# 15_HD_PUMP.net
KiCad netlist of a schematic drawn in Altium Designer
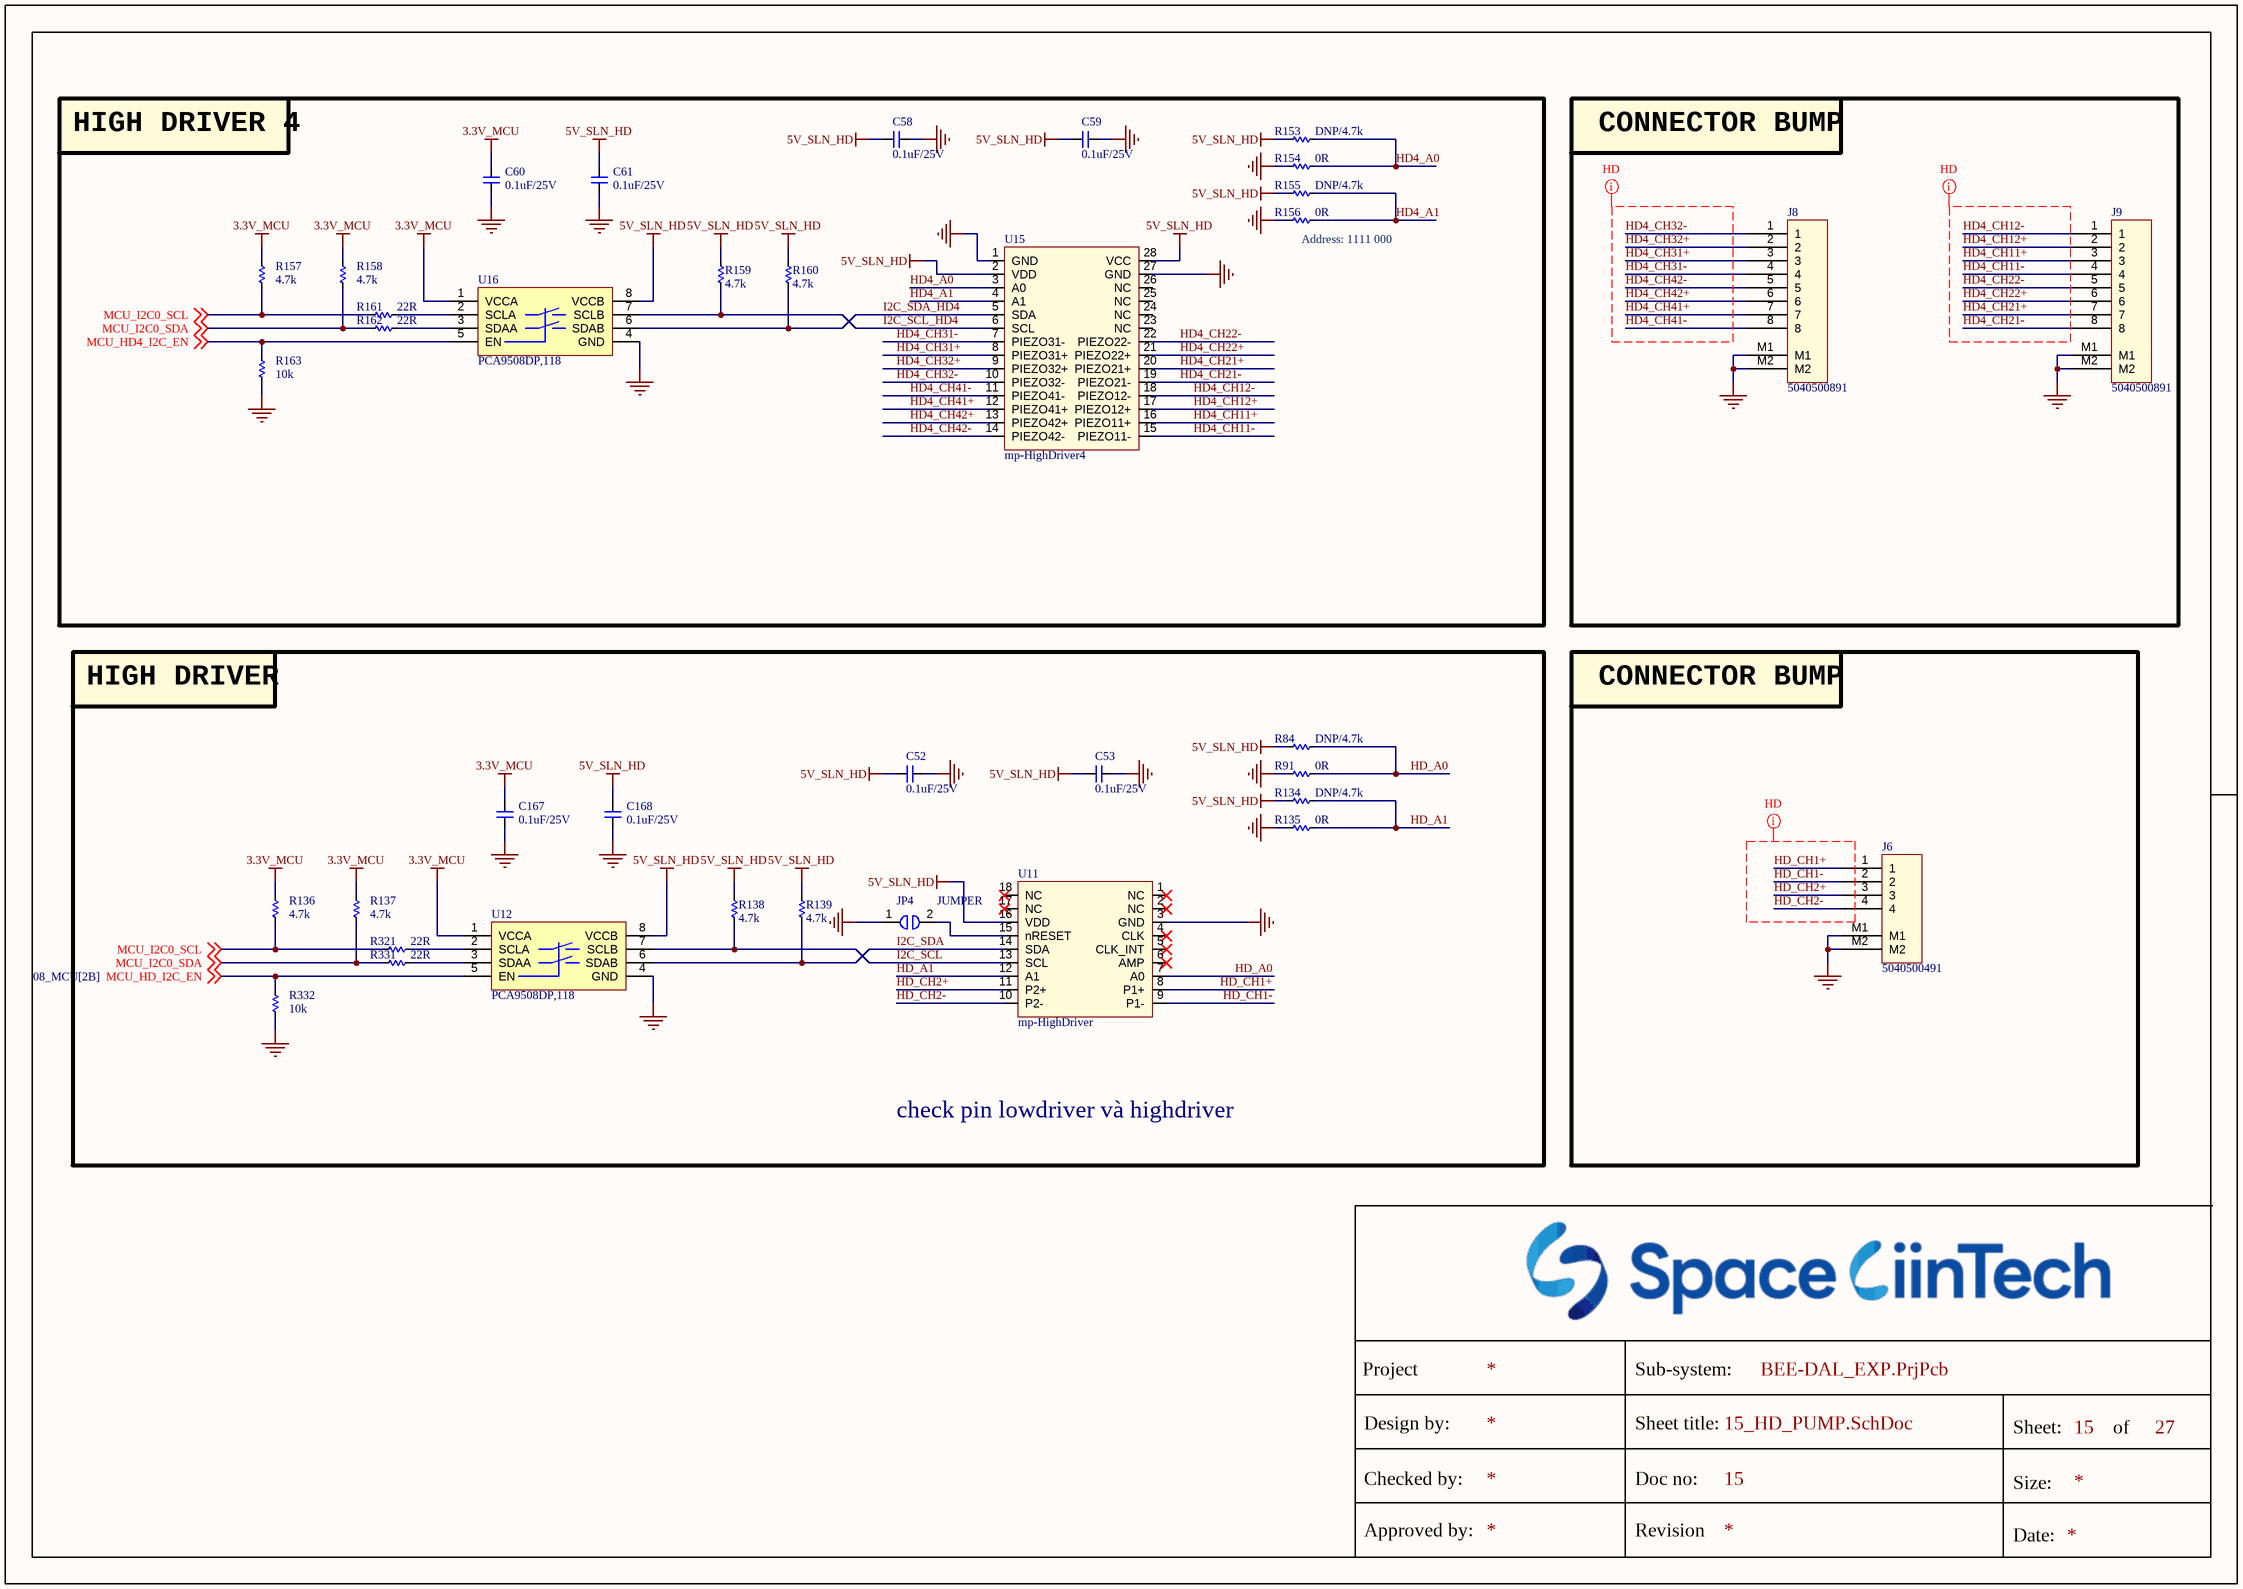
[diagram p0: 15_HD_PUMP.SchDoc]

(export (version "E")
  (design (tool "Eeschema 10.0.6"))
  (components
    (comp (ref "C52")
      (value "0.1uF/25V")
      (footprint "CAP_C_1005X60")
      (description "CAP")
      (libsource (lib "LABLIB") (part "_CAP_C_2"))
    )
    (comp (ref "C53")
      (value "0.1uF/25V")
      (footprint "CAP_C_1005X60")
      (description "CAP")
      (libsource (lib "LABLIB") (part "_CAP_C_2"))
    )
    (comp (ref "C58")
      (value "0.1uF/25V")
      (footprint "CAP_C_1005X60")
      (description "CAP")
      (libsource (lib "LABLIB") (part "_CAP_C_2"))
    )
    (comp (ref "C59")
      (value "0.1uF/25V")
      (footprint "CAP_C_1005X60")
      (description "CAP")
      (libsource (lib "LABLIB") (part "_CAP_C_2"))
    )
    (comp (ref "C60")
      (value "0.1uF/25V")
      (footprint "CAP_C_1005X60")
      (description "CAP")
      (libsource (lib "LABLIB") (part "_CAP_C_2"))
    )
    (comp (ref "C61")
      (value "0.1uF/25V")
      (footprint "CAP_C_1005X60")
      (description "CAP")
      (libsource (lib "LABLIB") (part "_CAP_C_2"))
    )
    (comp (ref "C167")
      (value "0.1uF/25V")
      (footprint "CAP_C_1005X60")
      (description "CAP")
      (libsource (lib "LABLIB") (part "_CAP_C_2"))
    )
    (comp (ref "C168")
      (value "0.1uF/25V")
      (footprint "CAP_C_1005X60")
      (description "CAP")
      (libsource (lib "LABLIB") (part "_CAP_C_2"))
    )
    (comp (ref "J6")
      (value "5040500491")
      (footprint "MOLEX_5040500491")
      (libsource (lib "LABLIB") (part "Header 4x1_2M"))
    )
    (comp (ref "J8")
      (value "5040500891")
      (footprint "MOLEX_5040500891")
      (libsource (lib "LABLIB") (part "Header 8x1_2M"))
    )
    (comp (ref "J9")
      (value "5040500891")
      (footprint "MOLEX_5040500891")
      (libsource (lib "LABLIB") (part "Header 8x1_2M"))
    )
    (comp (ref "JP4")
      (value "JUMPER")
      (footprint "JUMPER_1608")
      (libsource (lib "BEE-DAL_EXP_sche") (part "JUMPER_1_1"))
    )
    (comp (ref "R84")
      (value "DNP/4.7k")
      (footprint "RES_C_1005X40")
      (description "RES")
      (libsource (lib "LABLIB") (part "_RES_B_2"))
    )
    (comp (ref "R91")
      (value "0R")
      (footprint "RES_C_1005X40")
      (description "RES")
      (libsource (lib "LABLIB") (part "_RES_B_2"))
    )
    (comp (ref "R134")
      (value "DNP/4.7k")
      (footprint "RES_C_1005X40")
      (description "RES")
      (libsource (lib "LABLIB") (part "_RES_B_2"))
    )
    (comp (ref "R135")
      (value "0R")
      (footprint "RES_C_1005X40")
      (description "RES")
      (libsource (lib "LABLIB") (part "_RES_B_2"))
    )
    (comp (ref "R136")
      (value "4.7k")
      (footprint "RES_C_1005X40")
      (description "RES")
      (libsource (lib "LABLIB") (part "_RES_B_2"))
    )
    (comp (ref "R137")
      (value "4.7k")
      (footprint "RES_C_1005X40")
      (description "RES")
      (libsource (lib "LABLIB") (part "_RES_B_2"))
    )
    (comp (ref "R138")
      (value "4.7k")
      (footprint "RES_C_1005X40")
      (description "RES")
      (libsource (lib "LABLIB") (part "_RES_B_2"))
    )
    (comp (ref "R139")
      (value "4.7k")
      (footprint "RES_C_1005X40")
      (description "RES")
      (libsource (lib "LABLIB") (part "_RES_B_2"))
    )
    (comp (ref "R153")
      (value "DNP/4.7k")
      (footprint "RES_C_1005X40")
      (description "RES")
      (libsource (lib "LABLIB") (part "_RES_B_2"))
    )
    (comp (ref "R154")
      (value "0R")
      (footprint "RES_C_1005X40")
      (description "RES")
      (libsource (lib "LABLIB") (part "_RES_B_2"))
    )
    (comp (ref "R155")
      (value "DNP/4.7k")
      (footprint "RES_C_1005X40")
      (description "RES")
      (libsource (lib "LABLIB") (part "_RES_B_2"))
    )
    (comp (ref "R156")
      (value "0R")
      (footprint "RES_C_1005X40")
      (description "RES")
      (libsource (lib "LABLIB") (part "_RES_B_2"))
    )
    (comp (ref "R157")
      (value "4.7k")
      (footprint "RES_C_1005X40")
      (description "RES")
      (libsource (lib "LABLIB") (part "_RES_B_2"))
    )
    (comp (ref "R158")
      (value "4.7k")
      (footprint "RES_C_1005X40")
      (description "RES")
      (libsource (lib "LABLIB") (part "_RES_B_2"))
    )
    (comp (ref "R159")
      (value "4.7k")
      (footprint "RES_C_1005X40")
      (description "RES")
      (libsource (lib "LABLIB") (part "_RES_B_2"))
    )
    (comp (ref "R160")
      (value "4.7k")
      (footprint "RES_C_1005X40")
      (description "RES")
      (libsource (lib "LABLIB") (part "_RES_B_2"))
    )
    (comp (ref "R161")
      (value "22R")
      (footprint "RES_C_1005X40")
      (description "RES")
      (libsource (lib "LABLIB") (part "_RES_B_2"))
    )
    (comp (ref "R162")
      (value "22R")
      (footprint "RES_C_1005X40")
      (description "RES")
      (libsource (lib "LABLIB") (part "_RES_B_2"))
    )
    (comp (ref "R163")
      (value "10k")
      (footprint "RES_C_1005X40")
      (description "RES")
      (libsource (lib "LABLIB") (part "_RES_B_2"))
    )
    (comp (ref "R321")
      (value "22R")
      (footprint "RES_C_1005X40")
      (description "RES")
      (libsource (lib "LABLIB") (part "_RES_B_2"))
    )
    (comp (ref "R331")
      (value "22R")
      (footprint "RES_C_1005X40")
      (description "RES")
      (libsource (lib "LABLIB") (part "_RES_B_2"))
    )
    (comp (ref "R332")
      (value "10k")
      (footprint "RES_C_1005X40")
      (description "RES")
      (libsource (lib "LABLIB") (part "_RES_B_2"))
    )
    (comp (ref "U11")
      (value "mp-HighDriver")
      (footprint "MP_HIGHDRIVER")
      (libsource (lib "LABLIB") (part "mp-HighDriver"))
    )
    (comp (ref "U12")
      (value "PCA9508DP,118")
      (footprint "TSOP8")
      (libsource (lib "BEE-DAL_EXP_sche") (part "PCA9508DP,118"))
    )
    (comp (ref "U15")
      (value "mp-HighDriver4")
      (footprint "MP_HIGHDRIVER4")
      (libsource (lib "BEE-DAL_EXP_sche") (part "mp_HighDriver4"))
    )
    (comp (ref "U16")
      (value "PCA9508DP,118")
      (footprint "TSOP8")
      (libsource (lib "BEE-DAL_EXP_sche") (part "PCA9508DP,118"))
    )
  )
  (nets
    (net (code "1") (name "/HD4_A0") (class "Default")
      (node (ref "R153") (pin "2") (pinfunction "2_2") (pintype "passive"))
      (node (ref "R154") (pin "2") (pinfunction "2_2") (pintype "passive"))
      (node (ref "U15") (pin "3") (pinfunction "A0_3") (pintype "passive"))
    )
    (net (code "2") (name "/HD4_A1") (class "Default")
      (node (ref "R155") (pin "2") (pinfunction "2_2") (pintype "passive"))
      (node (ref "R156") (pin "2") (pinfunction "2_2") (pintype "passive"))
      (node (ref "U15") (pin "4") (pinfunction "A1_4") (pintype "passive"))
    )
    (net (code "3") (name "/HD4_CH11+") (class "Default")
      (node (ref "J9") (pin "3") (pinfunction "3_3") (pintype "passive"))
      (node (ref "U15") (pin "16") (pinfunction "PIEZO11+_16") (pintype "passive"))
    )
    (net (code "4") (name "/HD4_CH11-") (class "Default")
      (node (ref "J9") (pin "4") (pinfunction "4_4") (pintype "passive"))
      (node (ref "U15") (pin "15") (pinfunction "PIEZO11-_15") (pintype "passive"))
    )
    (net (code "5") (name "/HD4_CH12+") (class "Default")
      (node (ref "J9") (pin "2") (pinfunction "2_2") (pintype "passive"))
      (node (ref "U15") (pin "17") (pinfunction "PIEZO12+_17") (pintype "passive"))
    )
    (net (code "6") (name "/HD4_CH12-") (class "Default")
      (node (ref "J9") (pin "1") (pinfunction "1_1") (pintype "passive"))
      (node (ref "U15") (pin "18") (pinfunction "PIEZO12-_18") (pintype "passive"))
    )
    (net (code "7") (name "/HD4_CH21+") (class "Default")
      (node (ref "J9") (pin "7") (pinfunction "7_7") (pintype "passive"))
      (node (ref "U15") (pin "20") (pinfunction "PIEZO21+_20") (pintype "passive"))
    )
    (net (code "8") (name "/HD4_CH21-") (class "Default")
      (node (ref "J9") (pin "8") (pinfunction "8_8") (pintype "passive"))
      (node (ref "U15") (pin "19") (pinfunction "PIEZO21-_19") (pintype "passive"))
    )
    (net (code "9") (name "/HD4_CH22+") (class "Default")
      (node (ref "J9") (pin "6") (pinfunction "6_6") (pintype "passive"))
      (node (ref "U15") (pin "21") (pinfunction "PIEZO22+_21") (pintype "passive"))
    )
    (net (code "10") (name "/HD4_CH22-") (class "Default")
      (node (ref "J9") (pin "5") (pinfunction "5_5") (pintype "passive"))
      (node (ref "U15") (pin "22") (pinfunction "PIEZO22-_22") (pintype "passive"))
    )
    (net (code "11") (name "/HD4_CH31+") (class "Default")
      (node (ref "J8") (pin "3") (pinfunction "3_3") (pintype "passive"))
      (node (ref "U15") (pin "8") (pinfunction "PIEZO31+_8") (pintype "passive"))
    )
    (net (code "12") (name "/HD4_CH31-") (class "Default")
      (node (ref "J8") (pin "4") (pinfunction "4_4") (pintype "passive"))
      (node (ref "U15") (pin "7") (pinfunction "PIEZO31-_7") (pintype "passive"))
    )
    (net (code "13") (name "/HD4_CH32+") (class "Default")
      (node (ref "J8") (pin "2") (pinfunction "2_2") (pintype "passive"))
      (node (ref "U15") (pin "9") (pinfunction "PIEZO32+_9") (pintype "passive"))
    )
    (net (code "14") (name "/HD4_CH32-") (class "Default")
      (node (ref "J8") (pin "1") (pinfunction "1_1") (pintype "passive"))
      (node (ref "U15") (pin "10") (pinfunction "PIEZO32-_10") (pintype "passive"))
    )
    (net (code "15") (name "/HD4_CH41+") (class "Default")
      (node (ref "J8") (pin "7") (pinfunction "7_7") (pintype "passive"))
      (node (ref "U15") (pin "12") (pinfunction "PIEZO41+_12") (pintype "passive"))
    )
    (net (code "16") (name "/HD4_CH41-") (class "Default")
      (node (ref "J8") (pin "8") (pinfunction "8_8") (pintype "passive"))
      (node (ref "U15") (pin "11") (pinfunction "PIEZO41-_11") (pintype "passive"))
    )
    (net (code "17") (name "/HD4_CH42+") (class "Default")
      (node (ref "J8") (pin "6") (pinfunction "6_6") (pintype "passive"))
      (node (ref "U15") (pin "13") (pinfunction "PIEZO42+_13") (pintype "passive"))
    )
    (net (code "18") (name "/HD4_CH42-") (class "Default")
      (node (ref "J8") (pin "5") (pinfunction "5_5") (pintype "passive"))
      (node (ref "U15") (pin "14") (pinfunction "PIEZO42-_14") (pintype "passive"))
    )
    (net (code "19") (name "/HD_A0") (class "Default")
      (node (ref "R84") (pin "2") (pinfunction "2_2") (pintype "passive"))
      (node (ref "R91") (pin "2") (pinfunction "2_2") (pintype "passive"))
      (node (ref "U11") (pin "7") (pinfunction "A0_7") (pintype "passive"))
    )
    (net (code "20") (name "/HD_A1") (class "Default")
      (node (ref "R134") (pin "2") (pinfunction "2_2") (pintype "passive"))
      (node (ref "R135") (pin "2") (pinfunction "2_2") (pintype "passive"))
      (node (ref "U11") (pin "12") (pinfunction "A1_12") (pintype "passive"))
    )
    (net (code "21") (name "/HD_CH1+") (class "Default")
      (node (ref "J6") (pin "1") (pinfunction "1_1") (pintype "passive"))
      (node (ref "U11") (pin "8") (pinfunction "P1+_8") (pintype "passive"))
    )
    (net (code "22") (name "/HD_CH1-") (class "Default")
      (node (ref "J6") (pin "2") (pinfunction "2_2") (pintype "passive"))
      (node (ref "U11") (pin "9") (pinfunction "P1-_9") (pintype "passive"))
    )
    (net (code "23") (name "/HD_CH2+") (class "Default")
      (node (ref "J6") (pin "3") (pinfunction "3_3") (pintype "passive"))
      (node (ref "U11") (pin "11") (pinfunction "P2+_11") (pintype "passive"))
    )
    (net (code "24") (name "/HD_CH2-") (class "Default")
      (node (ref "J6") (pin "4") (pinfunction "4_4") (pintype "passive"))
      (node (ref "U11") (pin "10") (pinfunction "P2-_10") (pintype "passive"))
    )
    (net (code "25") (name "/I2C_SCL") (class "Default")
      (node (ref "R138") (pin "2") (pinfunction "2_2") (pintype "passive"))
      (node (ref "U11") (pin "13") (pinfunction "SCL_13") (pintype "passive"))
      (node (ref "U12") (pin "7") (pinfunction "SCLB_7") (pintype "passive"))
    )
    (net (code "26") (name "/I2C_SCL_HD4") (class "Default")
      (node (ref "R159") (pin "2") (pinfunction "2_2") (pintype "passive"))
      (node (ref "U15") (pin "6") (pinfunction "SCL_6") (pintype "passive"))
      (node (ref "U16") (pin "7") (pinfunction "SCLB_7") (pintype "passive"))
    )
    (net (code "27") (name "/I2C_SDA") (class "Default")
      (node (ref "R139") (pin "2") (pinfunction "2_2") (pintype "passive"))
      (node (ref "U11") (pin "14") (pinfunction "SDA_14") (pintype "passive"))
      (node (ref "U12") (pin "6") (pinfunction "SDAB_6") (pintype "passive"))
    )
    (net (code "28") (name "/I2C_SDA_HD4") (class "Default")
      (node (ref "R160") (pin "2") (pinfunction "2_2") (pintype "passive"))
      (node (ref "U15") (pin "5") (pinfunction "SDA_5") (pintype "passive"))
      (node (ref "U16") (pin "6") (pinfunction "SDAB_6") (pintype "passive"))
    )
    (net (code "29") (name "3.3V_MCU") (class "Default")
      (node (ref "C167") (pin "2") (pinfunction "2_2") (pintype "passive"))
      (node (ref "C60") (pin "2") (pinfunction "2_2") (pintype "passive"))
      (node (ref "R136") (pin "1") (pinfunction "1_1") (pintype "passive"))
      (node (ref "R137") (pin "1") (pinfunction "1_1") (pintype "passive"))
      (node (ref "R157") (pin "1") (pinfunction "1_1") (pintype "passive"))
      (node (ref "R158") (pin "1") (pinfunction "1_1") (pintype "passive"))
      (node (ref "U12") (pin "1") (pinfunction "VCCA_1") (pintype "passive"))
      (node (ref "U16") (pin "1") (pinfunction "VCCA_1") (pintype "passive"))
    )
    (net (code "30") (name "5V_SLN_HD") (class "Default")
      (node (ref "C168") (pin "2") (pinfunction "2_2") (pintype "passive"))
      (node (ref "C52") (pin "2") (pinfunction "2_2") (pintype "passive"))
      (node (ref "C53") (pin "2") (pinfunction "2_2") (pintype "passive"))
      (node (ref "C58") (pin "2") (pinfunction "2_2") (pintype "passive"))
      (node (ref "C59") (pin "2") (pinfunction "2_2") (pintype "passive"))
      (node (ref "C61") (pin "2") (pinfunction "2_2") (pintype "passive"))
      (node (ref "R134") (pin "1") (pinfunction "1_1") (pintype "passive"))
      (node (ref "R138") (pin "1") (pinfunction "1_1") (pintype "passive"))
      (node (ref "R139") (pin "1") (pinfunction "1_1") (pintype "passive"))
      (node (ref "R153") (pin "1") (pinfunction "1_1") (pintype "passive"))
      (node (ref "R155") (pin "1") (pinfunction "1_1") (pintype "passive"))
      (node (ref "R159") (pin "1") (pinfunction "1_1") (pintype "passive"))
      (node (ref "R160") (pin "1") (pinfunction "1_1") (pintype "passive"))
      (node (ref "R84") (pin "1") (pinfunction "1_1") (pintype "passive"))
      (node (ref "U11") (pin "16") (pinfunction "VDD_16") (pintype "power_in"))
      (node (ref "U12") (pin "8") (pinfunction "VCCB_8") (pintype "passive"))
      (node (ref "U15") (pin "2") (pinfunction "VDD_2") (pintype "power_in"))
      (node (ref "U15") (pin "28") (pinfunction "VCC_28") (pintype "power_in"))
      (node (ref "U16") (pin "8") (pinfunction "VCCB_8") (pintype "passive"))
    )
    (net (code "31") (name "GND") (class "Default")
      (node (ref "C167") (pin "1") (pinfunction "1_1") (pintype "passive"))
      (node (ref "C168") (pin "1") (pinfunction "1_1") (pintype "passive"))
      (node (ref "C52") (pin "1") (pinfunction "1_1") (pintype "passive"))
      (node (ref "C53") (pin "1") (pinfunction "1_1") (pintype "passive"))
      (node (ref "C58") (pin "1") (pinfunction "1_1") (pintype "passive"))
      (node (ref "C59") (pin "1") (pinfunction "1_1") (pintype "passive"))
      (node (ref "C60") (pin "1") (pinfunction "1_1") (pintype "passive"))
      (node (ref "C61") (pin "1") (pinfunction "1_1") (pintype "passive"))
      (node (ref "J6") (pin "M1") (pinfunction "M1_M1") (pintype "passive"))
      (node (ref "J6") (pin "M2") (pinfunction "M2_M2") (pintype "passive"))
      (node (ref "J8") (pin "M1") (pinfunction "M1_M1") (pintype "passive"))
      (node (ref "J8") (pin "M2") (pinfunction "M2_M2") (pintype "passive"))
      (node (ref "J9") (pin "M1") (pinfunction "M1_M1") (pintype "passive"))
      (node (ref "J9") (pin "M2") (pinfunction "M2_M2") (pintype "passive"))
      (node (ref "JP4") (pin "1") (pinfunction "1_1") (pintype "passive"))
      (node (ref "R135") (pin "1") (pinfunction "1_1") (pintype "passive"))
      (node (ref "R154") (pin "1") (pinfunction "1_1") (pintype "passive"))
      (node (ref "R156") (pin "1") (pinfunction "1_1") (pintype "passive"))
      (node (ref "R163") (pin "2") (pinfunction "2_2") (pintype "passive"))
      (node (ref "R332") (pin "2") (pinfunction "2_2") (pintype "passive"))
      (node (ref "R91") (pin "1") (pinfunction "1_1") (pintype "passive"))
      (node (ref "U11") (pin "3") (pinfunction "GND_3") (pintype "power_in"))
      (node (ref "U12") (pin "4") (pinfunction "GND_4") (pintype "passive"))
      (node (ref "U15") (pin "1") (pinfunction "GND_1") (pintype "power_in"))
      (node (ref "U15") (pin "27") (pinfunction "GND_27") (pintype "power_in"))
      (node (ref "U16") (pin "4") (pinfunction "GND_4") (pintype "passive"))
    )
    (net (code "32") (name "MCU_HD4_I2C_EN") (class "Default")
      (node (ref "R163") (pin "1") (pinfunction "1_1") (pintype "passive"))
      (node (ref "U16") (pin "5") (pinfunction "EN_5") (pintype "passive"))
    )
    (net (code "33") (name "MCU_HD_I2C_EN") (class "Default")
      (node (ref "R332") (pin "1") (pinfunction "1_1") (pintype "passive"))
      (node (ref "U12") (pin "5") (pinfunction "EN_5") (pintype "passive"))
    )
    (net (code "34") (name "MCU_I2C0_SCL") (class "Default")
      (node (ref "R136") (pin "2") (pinfunction "2_2") (pintype "passive"))
      (node (ref "R157") (pin "2") (pinfunction "2_2") (pintype "passive"))
      (node (ref "R161") (pin "1") (pinfunction "1_1") (pintype "passive"))
      (node (ref "R321") (pin "1") (pinfunction "1_1") (pintype "passive"))
    )
    (net (code "35") (name "MCU_I2C0_SDA") (class "Default")
      (node (ref "R137") (pin "2") (pinfunction "2_2") (pintype "passive"))
      (node (ref "R158") (pin "2") (pinfunction "2_2") (pintype "passive"))
      (node (ref "R162") (pin "1") (pinfunction "1_1") (pintype "passive"))
      (node (ref "R331") (pin "1") (pinfunction "1_1") (pintype "passive"))
    )
    (net (code "36") (name "Net-(U11-nRESET)") (class "Default")
      (node (ref "JP4") (pin "2") (pinfunction "2_2") (pintype "passive"))
      (node (ref "U11") (pin "15") (pinfunction "nRESET_15") (pintype "passive"))
    )
    (net (code "37") (name "Net-(U12-SCLA)") (class "Default")
      (node (ref "R321") (pin "2") (pinfunction "2_2") (pintype "passive"))
      (node (ref "U12") (pin "2") (pinfunction "SCLA_2") (pintype "passive"))
    )
    (net (code "38") (name "Net-(U12-SDAA)") (class "Default")
      (node (ref "R331") (pin "2") (pinfunction "2_2") (pintype "passive"))
      (node (ref "U12") (pin "3") (pinfunction "SDAA_3") (pintype "passive"))
    )
    (net (code "39") (name "Net-(U16-SCLA)") (class "Default")
      (node (ref "R161") (pin "2") (pinfunction "2_2") (pintype "passive"))
      (node (ref "U16") (pin "2") (pinfunction "SCLA_2") (pintype "passive"))
    )
    (net (code "40") (name "Net-(U16-SDAA)") (class "Default")
      (node (ref "R162") (pin "2") (pinfunction "2_2") (pintype "passive"))
      (node (ref "U16") (pin "3") (pinfunction "SDAA_3") (pintype "passive"))
    )
    (net (code "41") (name "unconnected-(U11-AMP-Pad6)") (class "Default")
      (node (ref "U11") (pin "6") (pinfunction "AMP_6") (pintype "passive+no_connect"))
    )
    (net (code "42") (name "unconnected-(U11-CLK-Pad4)") (class "Default")
      (node (ref "U11") (pin "4") (pinfunction "CLK_4") (pintype "passive+no_connect"))
    )
    (net (code "43") (name "unconnected-(U11-CLK_INT-Pad5)") (class "Default")
      (node (ref "U11") (pin "5") (pinfunction "CLK_INT_5") (pintype "passive+no_connect"))
    )
    (net (code "44") (name "unconnected-(U11-NC-Pad1)") (class "Default")
      (node (ref "U11") (pin "1") (pinfunction "NC_1") (pintype "passive+no_connect"))
    )
    (net (code "45") (name "unconnected-(U11-NC-Pad2)") (class "Default")
      (node (ref "U11") (pin "2") (pinfunction "NC_2") (pintype "passive+no_connect"))
    )
    (net (code "46") (name "unconnected-(U11-NC-Pad17)") (class "Default")
      (node (ref "U11") (pin "17") (pinfunction "NC_17") (pintype "passive+no_connect"))
    )
    (net (code "47") (name "unconnected-(U11-NC-Pad18)") (class "Default")
      (node (ref "U11") (pin "18") (pinfunction "NC_18") (pintype "passive+no_connect"))
    )
    (net (code "48") (name "unconnected-(U15-NC-Pad23)") (class "Default")
      (node (ref "U15") (pin "23") (pinfunction "NC_23") (pintype "passive"))
    )
    (net (code "49") (name "unconnected-(U15-NC-Pad24)") (class "Default")
      (node (ref "U15") (pin "24") (pinfunction "NC_24") (pintype "passive"))
    )
    (net (code "50") (name "unconnected-(U15-NC-Pad25)") (class "Default")
      (node (ref "U15") (pin "25") (pinfunction "NC_25") (pintype "passive"))
    )
    (net (code "51") (name "unconnected-(U15-NC-Pad26)") (class "Default")
      (node (ref "U15") (pin "26") (pinfunction "NC_26") (pintype "passive"))
    )
  )
)
